# CircuitSupply.net
KiCad netlist of a schematic drawn in EasyEDA Pro
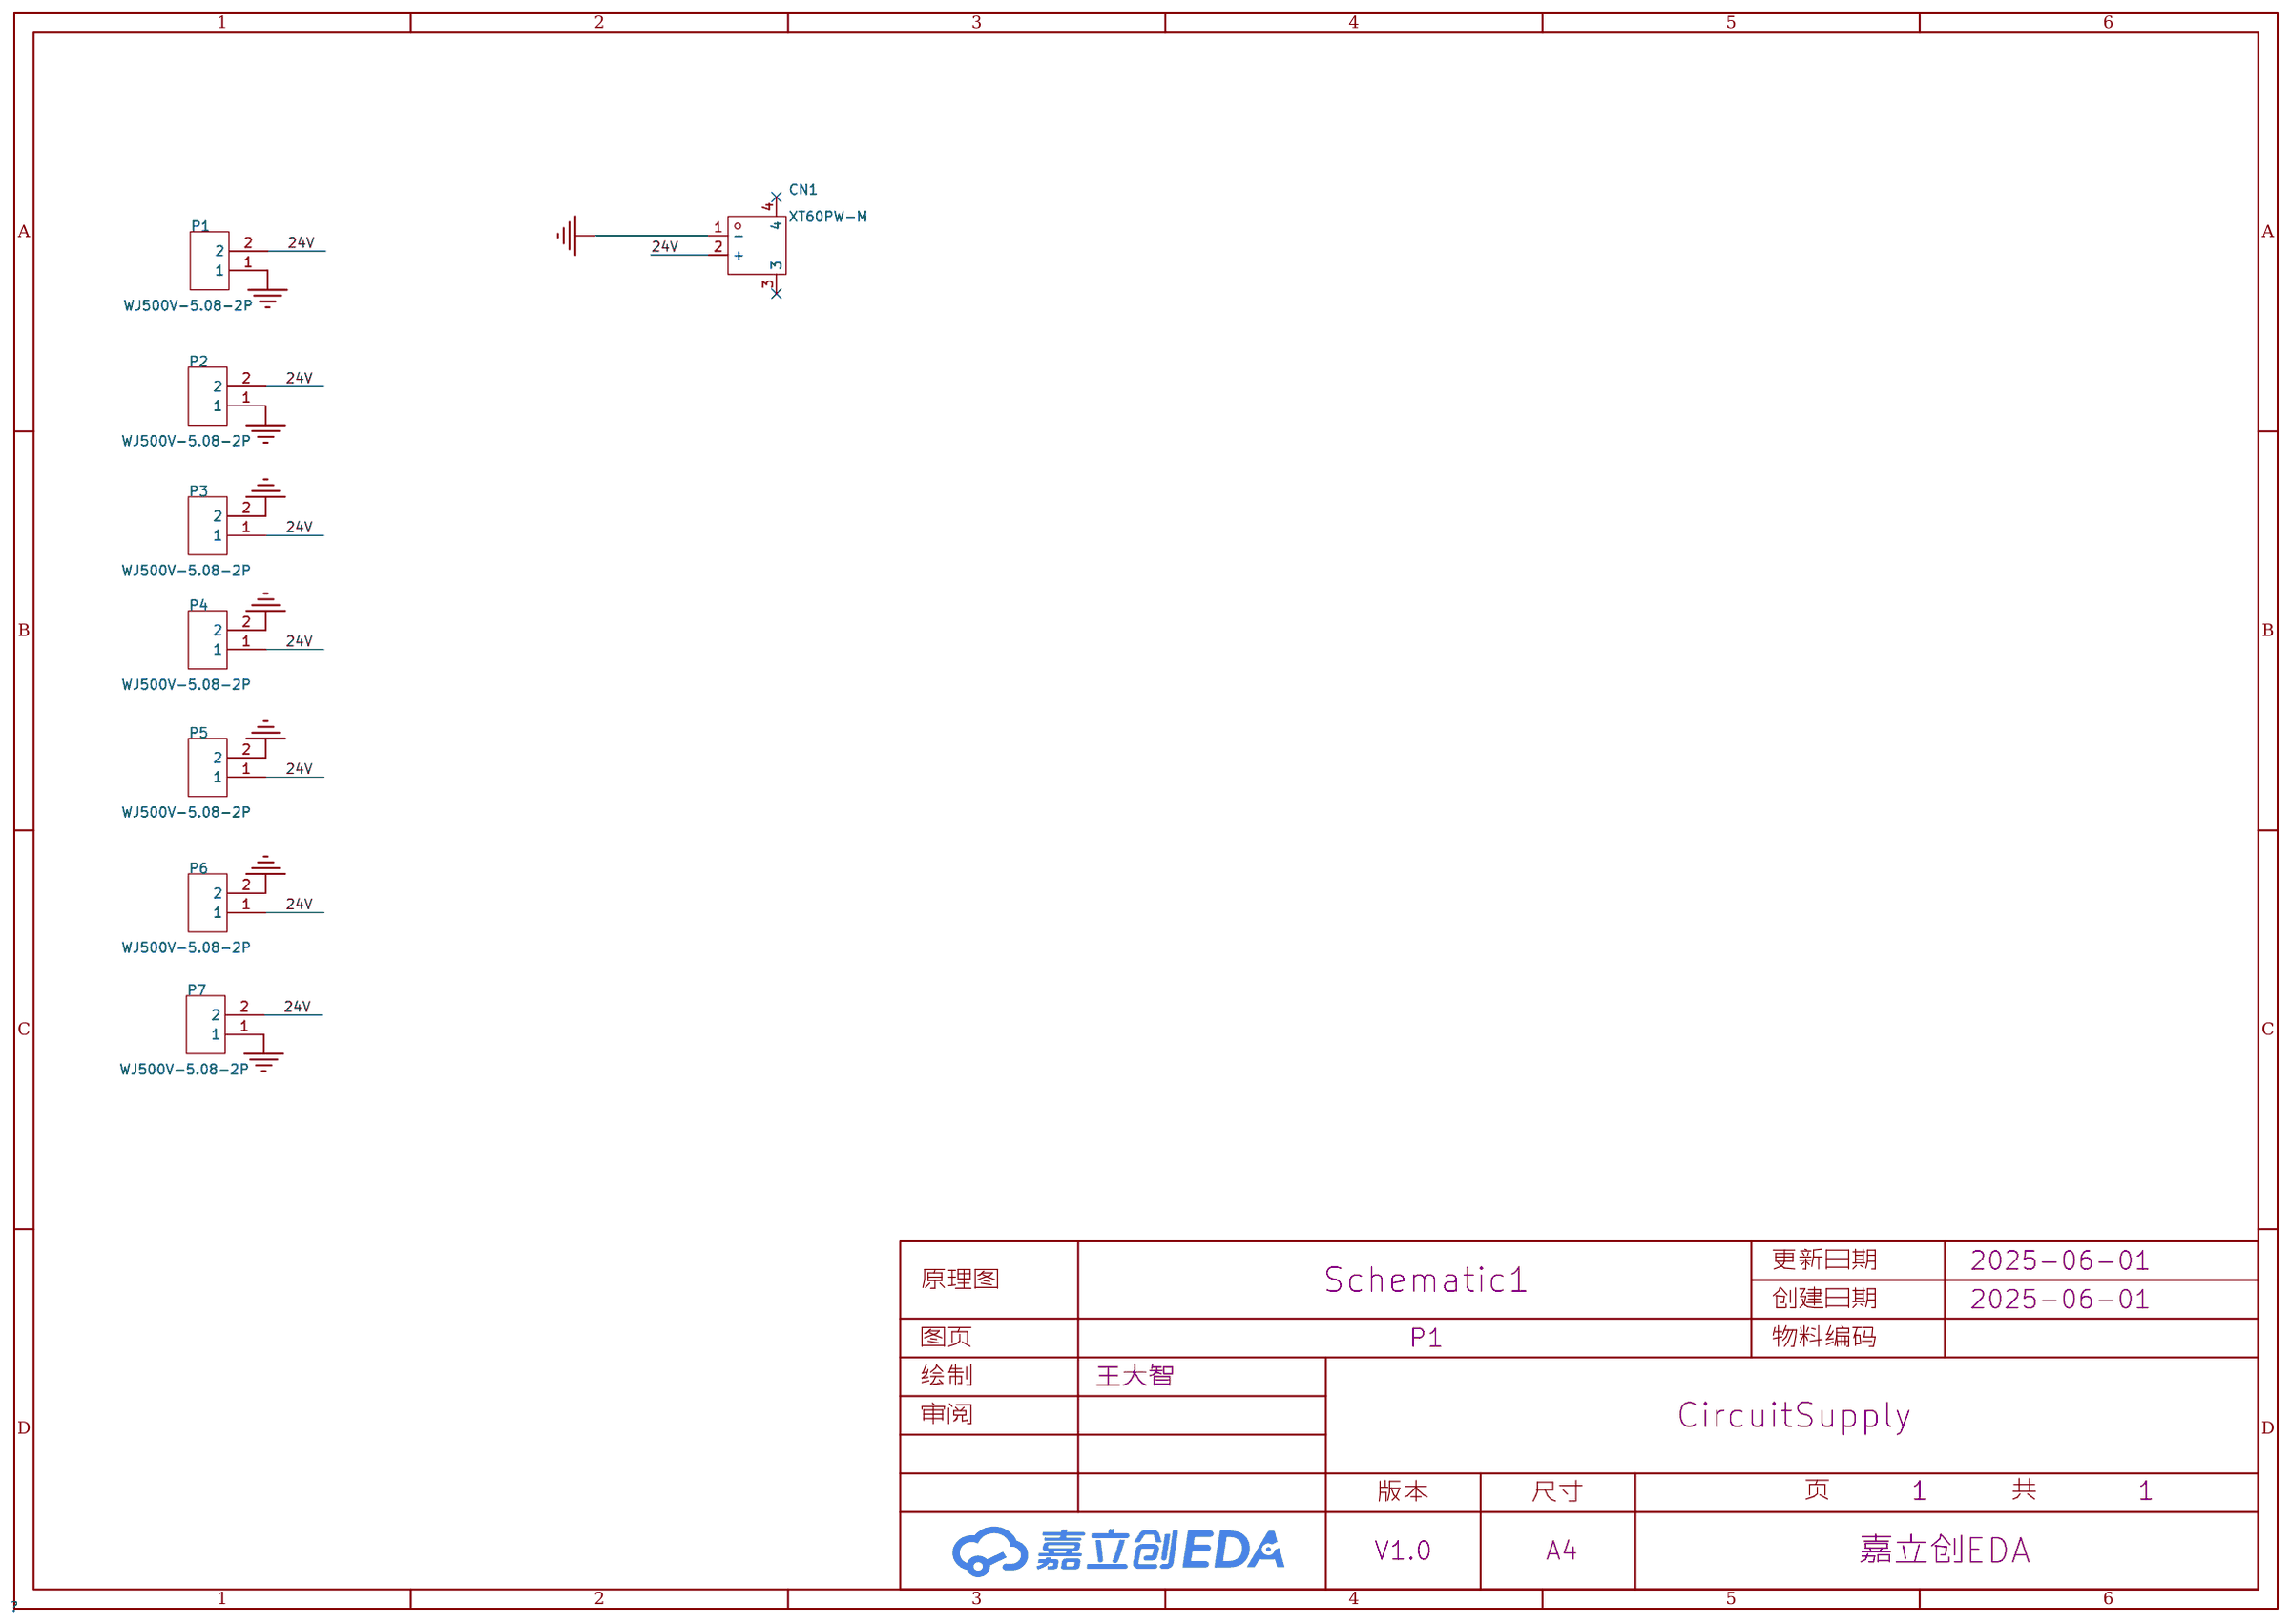
[diagram p0: schematic sheet]

(export (version "E")
  (design (tool "Eeschema 10.0.6"))
  (components
    (comp (ref "CN1")
      (value "XT60PW-M")
      (footprint "easyedapro:CONN-TH_XT60PW-M")
      (description "类别:-;类型1:-;")
      (fields (field (name "Manufacturer") "AMASS(艾迈斯)"))
      (libsource (lib "easyedapro") (part "XT60PW-M"))
    )
    (comp (ref "P1")
      (value "WJ500V-5.08-2P")
      (footprint "easyedapro:CONN-TH_2P-P5.00_WJ500V-5.08-2P")
      (fields (field (name "Manufacturer") "KANGNEX(康奈克斯电气)"))
      (libsource (lib "easyedapro") (part "WJ500V-5.08-2P-14-00A"))
    )
    (comp (ref "P2")
      (value "WJ500V-5.08-2P")
      (footprint "easyedapro:CONN-TH_2P-P5.00_WJ500V-5.08-2P")
      (fields (field (name "Manufacturer") "KANGNEX(康奈克斯电气)"))
      (libsource (lib "easyedapro") (part "WJ500V-5.08-2P-14-00A"))
    )
    (comp (ref "P3")
      (value "WJ500V-5.08-2P")
      (footprint "easyedapro:CONN-TH_2P-P5.00_WJ500V-5.08-2P")
      (fields (field (name "Manufacturer") "KANGNEX(康奈克斯电气)"))
      (libsource (lib "easyedapro") (part "WJ500V-5.08-2P-14-00A"))
    )
    (comp (ref "P4")
      (value "WJ500V-5.08-2P")
      (footprint "easyedapro:CONN-TH_2P-P5.00_WJ500V-5.08-2P")
      (fields (field (name "Manufacturer") "KANGNEX(康奈克斯电气)"))
      (libsource (lib "easyedapro") (part "WJ500V-5.08-2P-14-00A"))
    )
    (comp (ref "P5")
      (value "WJ500V-5.08-2P")
      (footprint "easyedapro:CONN-TH_2P-P5.00_WJ500V-5.08-2P")
      (fields (field (name "Manufacturer") "KANGNEX(康奈克斯电气)"))
      (libsource (lib "easyedapro") (part "WJ500V-5.08-2P-14-00A"))
    )
    (comp (ref "P6")
      (value "WJ500V-5.08-2P")
      (footprint "easyedapro:CONN-TH_2P-P5.00_WJ500V-5.08-2P")
      (fields (field (name "Manufacturer") "KANGNEX(康奈克斯电气)"))
      (libsource (lib "easyedapro") (part "WJ500V-5.08-2P-14-00A"))
    )
    (comp (ref "P7")
      (value "WJ500V-5.08-2P")
      (footprint "easyedapro:CONN-TH_2P-P5.00_WJ500V-5.08-2P")
      (fields (field (name "Manufacturer") "KANGNEX(康奈克斯电气)"))
      (libsource (lib "easyedapro") (part "WJ500V-5.08-2P-14-00A"))
    )
  )
  (nets
    (net (code "1") (name "/24V") (class "Default")
      (node (ref "CN1") (pin "2") (pinfunction "+_2") (pintype "unspecified"))
      (node (ref "P1") (pin "2") (pinfunction "2_2") (pintype "unspecified"))
      (node (ref "P2") (pin "2") (pinfunction "2_2") (pintype "unspecified"))
      (node (ref "P3") (pin "1") (pinfunction "1_1") (pintype "unspecified"))
      (node (ref "P4") (pin "1") (pinfunction "1_1") (pintype "unspecified"))
      (node (ref "P5") (pin "1") (pinfunction "1_1") (pintype "unspecified"))
      (node (ref "P6") (pin "1") (pinfunction "1_1") (pintype "unspecified"))
      (node (ref "P7") (pin "2") (pinfunction "2_2") (pintype "unspecified"))
    )
    (net (code "2") (name "GND") (class "Default")
      (node (ref "CN1") (pin "1") (pinfunction "-_1") (pintype "unspecified"))
      (node (ref "P1") (pin "1") (pinfunction "1_1") (pintype "unspecified"))
      (node (ref "P2") (pin "1") (pinfunction "1_1") (pintype "unspecified"))
      (node (ref "P3") (pin "2") (pinfunction "2_2") (pintype "unspecified"))
      (node (ref "P4") (pin "2") (pinfunction "2_2") (pintype "unspecified"))
      (node (ref "P5") (pin "2") (pinfunction "2_2") (pintype "unspecified"))
      (node (ref "P6") (pin "2") (pinfunction "2_2") (pintype "unspecified"))
      (node (ref "P7") (pin "1") (pinfunction "1_1") (pintype "unspecified"))
    )
    (net (code "3") (name "unconnected-(CN1-Pad3)") (class "Default")
      (node (ref "CN1") (pin "3") (pinfunction "3_3") (pintype "unspecified+no_connect"))
    )
    (net (code "4") (name "unconnected-(CN1-Pad4)") (class "Default")
      (node (ref "CN1") (pin "4") (pinfunction "4_4") (pintype "unspecified+no_connect"))
    )
  )
)
